# mainboard_wifi_v1_6.net
KiCad netlist of a schematic drawn in Altium Designer
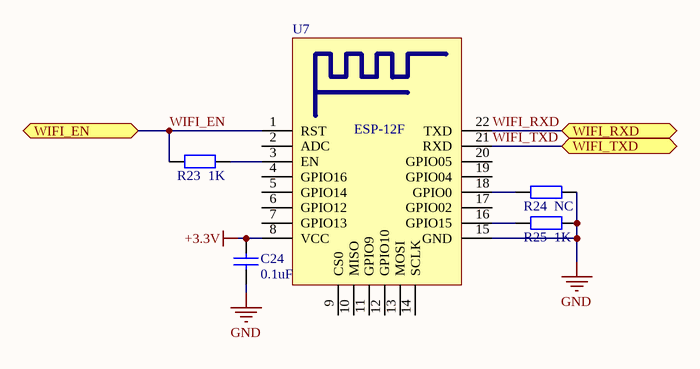
[diagram p0: mainboard_wifi.v1.6.SchDoc]

(export (version "E")
  (design (tool "Eeschema 10.0.6"))
  (components
    (comp (ref "C24")
      (value "0.1uF")
      (footprint "0805")
      (description "Capacitor")
      (libsource (lib "Miscellaneous Devices") (part "Cap"))
    )
    (comp (ref "R23")
      (value "1K")
      (footprint "0805")
      (description "Resistor")
      (libsource (lib "Miscellaneous Devices") (part "Res2"))
    )
    (comp (ref "R24")
      (value "NC")
      (footprint "0805")
      (description "Resistor")
      (libsource (lib "Miscellaneous Devices") (part "Res2"))
    )
    (comp (ref "R25")
      (value "1K")
      (footprint "0805")
      (description "Resistor")
      (libsource (lib "Miscellaneous Devices") (part "Res2"))
    )
    (comp (ref "U7") (value "ESP-12F") (footprint "ESP-12F") (libsource (lib "Componet") (part "ESP-12F")))
  )
  (nets
    (net (code "1") (name "+3.3V") (class "Default")
      (node (ref "C24") (pin "2") (pinfunction "2_2") (pintype "passive"))
      (node (ref "U7") (pin "8") (pinfunction "VCC_8") (pintype "passive"))
    )
    (net (code "2") (name "/WIFI_EN") (class "Default")
      (node (ref "R23") (pin "1") (pinfunction "1_1") (pintype "passive"))
      (node (ref "U7") (pin "1") (pinfunction "RST_1") (pintype "passive"))
    )
    (net (code "3") (name "/WIFI_RXD") (class "Default")
      (node (ref "U7") (pin "22") (pinfunction "TXD_22") (pintype "passive"))
    )
    (net (code "4") (name "/WIFI_TXD") (class "Default")
      (node (ref "U7") (pin "21") (pinfunction "RXD_21") (pintype "passive"))
    )
    (net (code "5") (name "GND") (class "Default")
      (node (ref "C24") (pin "1") (pinfunction "1_1") (pintype "passive"))
      (node (ref "R24") (pin "2") (pinfunction "2_2") (pintype "passive"))
      (node (ref "R25") (pin "2") (pinfunction "2_2") (pintype "passive"))
      (node (ref "U7") (pin "15") (pinfunction "GND_15") (pintype "passive"))
    )
    (net (code "6") (name "Net-(U7-EN)") (class "Default")
      (node (ref "R23") (pin "2") (pinfunction "2_2") (pintype "passive"))
      (node (ref "U7") (pin "3") (pinfunction "EN_3") (pintype "passive"))
    )
    (net (code "7") (name "Net-(U7-GPIO0)") (class "Default")
      (node (ref "R24") (pin "1") (pinfunction "1_1") (pintype "passive"))
      (node (ref "U7") (pin "18") (pinfunction "GPIO0_18") (pintype "passive"))
    )
    (net (code "8") (name "Net-(U7-GPIO15)") (class "Default")
      (node (ref "R25") (pin "1") (pinfunction "1_1") (pintype "passive"))
      (node (ref "U7") (pin "16") (pinfunction "GPIO15_16") (pintype "passive"))
    )
    (net (code "9") (name "unconnected-(U7-ADC-Pad2)") (class "Default")
      (node (ref "U7") (pin "2") (pinfunction "ADC_2") (pintype "passive"))
    )
    (net (code "10") (name "unconnected-(U7-CS0-Pad9)") (class "Default")
      (node (ref "U7") (pin "9") (pinfunction "CS0_9") (pintype "passive"))
    )
    (net (code "11") (name "unconnected-(U7-GPIO02-Pad17)") (class "Default")
      (node (ref "U7") (pin "17") (pinfunction "GPIO02_17") (pintype "passive"))
    )
    (net (code "12") (name "unconnected-(U7-GPIO04-Pad19)") (class "Default")
      (node (ref "U7") (pin "19") (pinfunction "GPIO04_19") (pintype "passive"))
    )
    (net (code "13") (name "unconnected-(U7-GPIO05-Pad20)") (class "Default")
      (node (ref "U7") (pin "20") (pinfunction "GPIO05_20") (pintype "passive"))
    )
    (net (code "14") (name "unconnected-(U7-GPIO9-Pad11)") (class "Default")
      (node (ref "U7") (pin "11") (pinfunction "GPIO9_11") (pintype "passive"))
    )
    (net (code "15") (name "unconnected-(U7-GPIO10-Pad12)") (class "Default")
      (node (ref "U7") (pin "12") (pinfunction "GPIO10_12") (pintype "passive"))
    )
    (net (code "16") (name "unconnected-(U7-GPIO12-Pad6)") (class "Default")
      (node (ref "U7") (pin "6") (pinfunction "GPIO12_6") (pintype "passive"))
    )
    (net (code "17") (name "unconnected-(U7-GPIO13-Pad7)") (class "Default")
      (node (ref "U7") (pin "7") (pinfunction "GPIO13_7") (pintype "passive"))
    )
    (net (code "18") (name "unconnected-(U7-GPIO14-Pad5)") (class "Default")
      (node (ref "U7") (pin "5") (pinfunction "GPIO14_5") (pintype "passive"))
    )
    (net (code "19") (name "unconnected-(U7-GPIO16-Pad4)") (class "Default")
      (node (ref "U7") (pin "4") (pinfunction "GPIO16_4") (pintype "passive"))
    )
    (net (code "20") (name "unconnected-(U7-MISO-Pad10)") (class "Default")
      (node (ref "U7") (pin "10") (pinfunction "MISO_10") (pintype "passive"))
    )
    (net (code "21") (name "unconnected-(U7-MOSI-Pad13)") (class "Default")
      (node (ref "U7") (pin "13") (pinfunction "MOSI_13") (pintype "passive"))
    )
    (net (code "22") (name "unconnected-(U7-SCLK-Pad14)") (class "Default")
      (node (ref "U7") (pin "14") (pinfunction "SCLK_14") (pintype "passive"))
    )
  )
)
